# P16_USB_3_0_HUB.net
KiCad netlist of a schematic drawn in Altium Designer
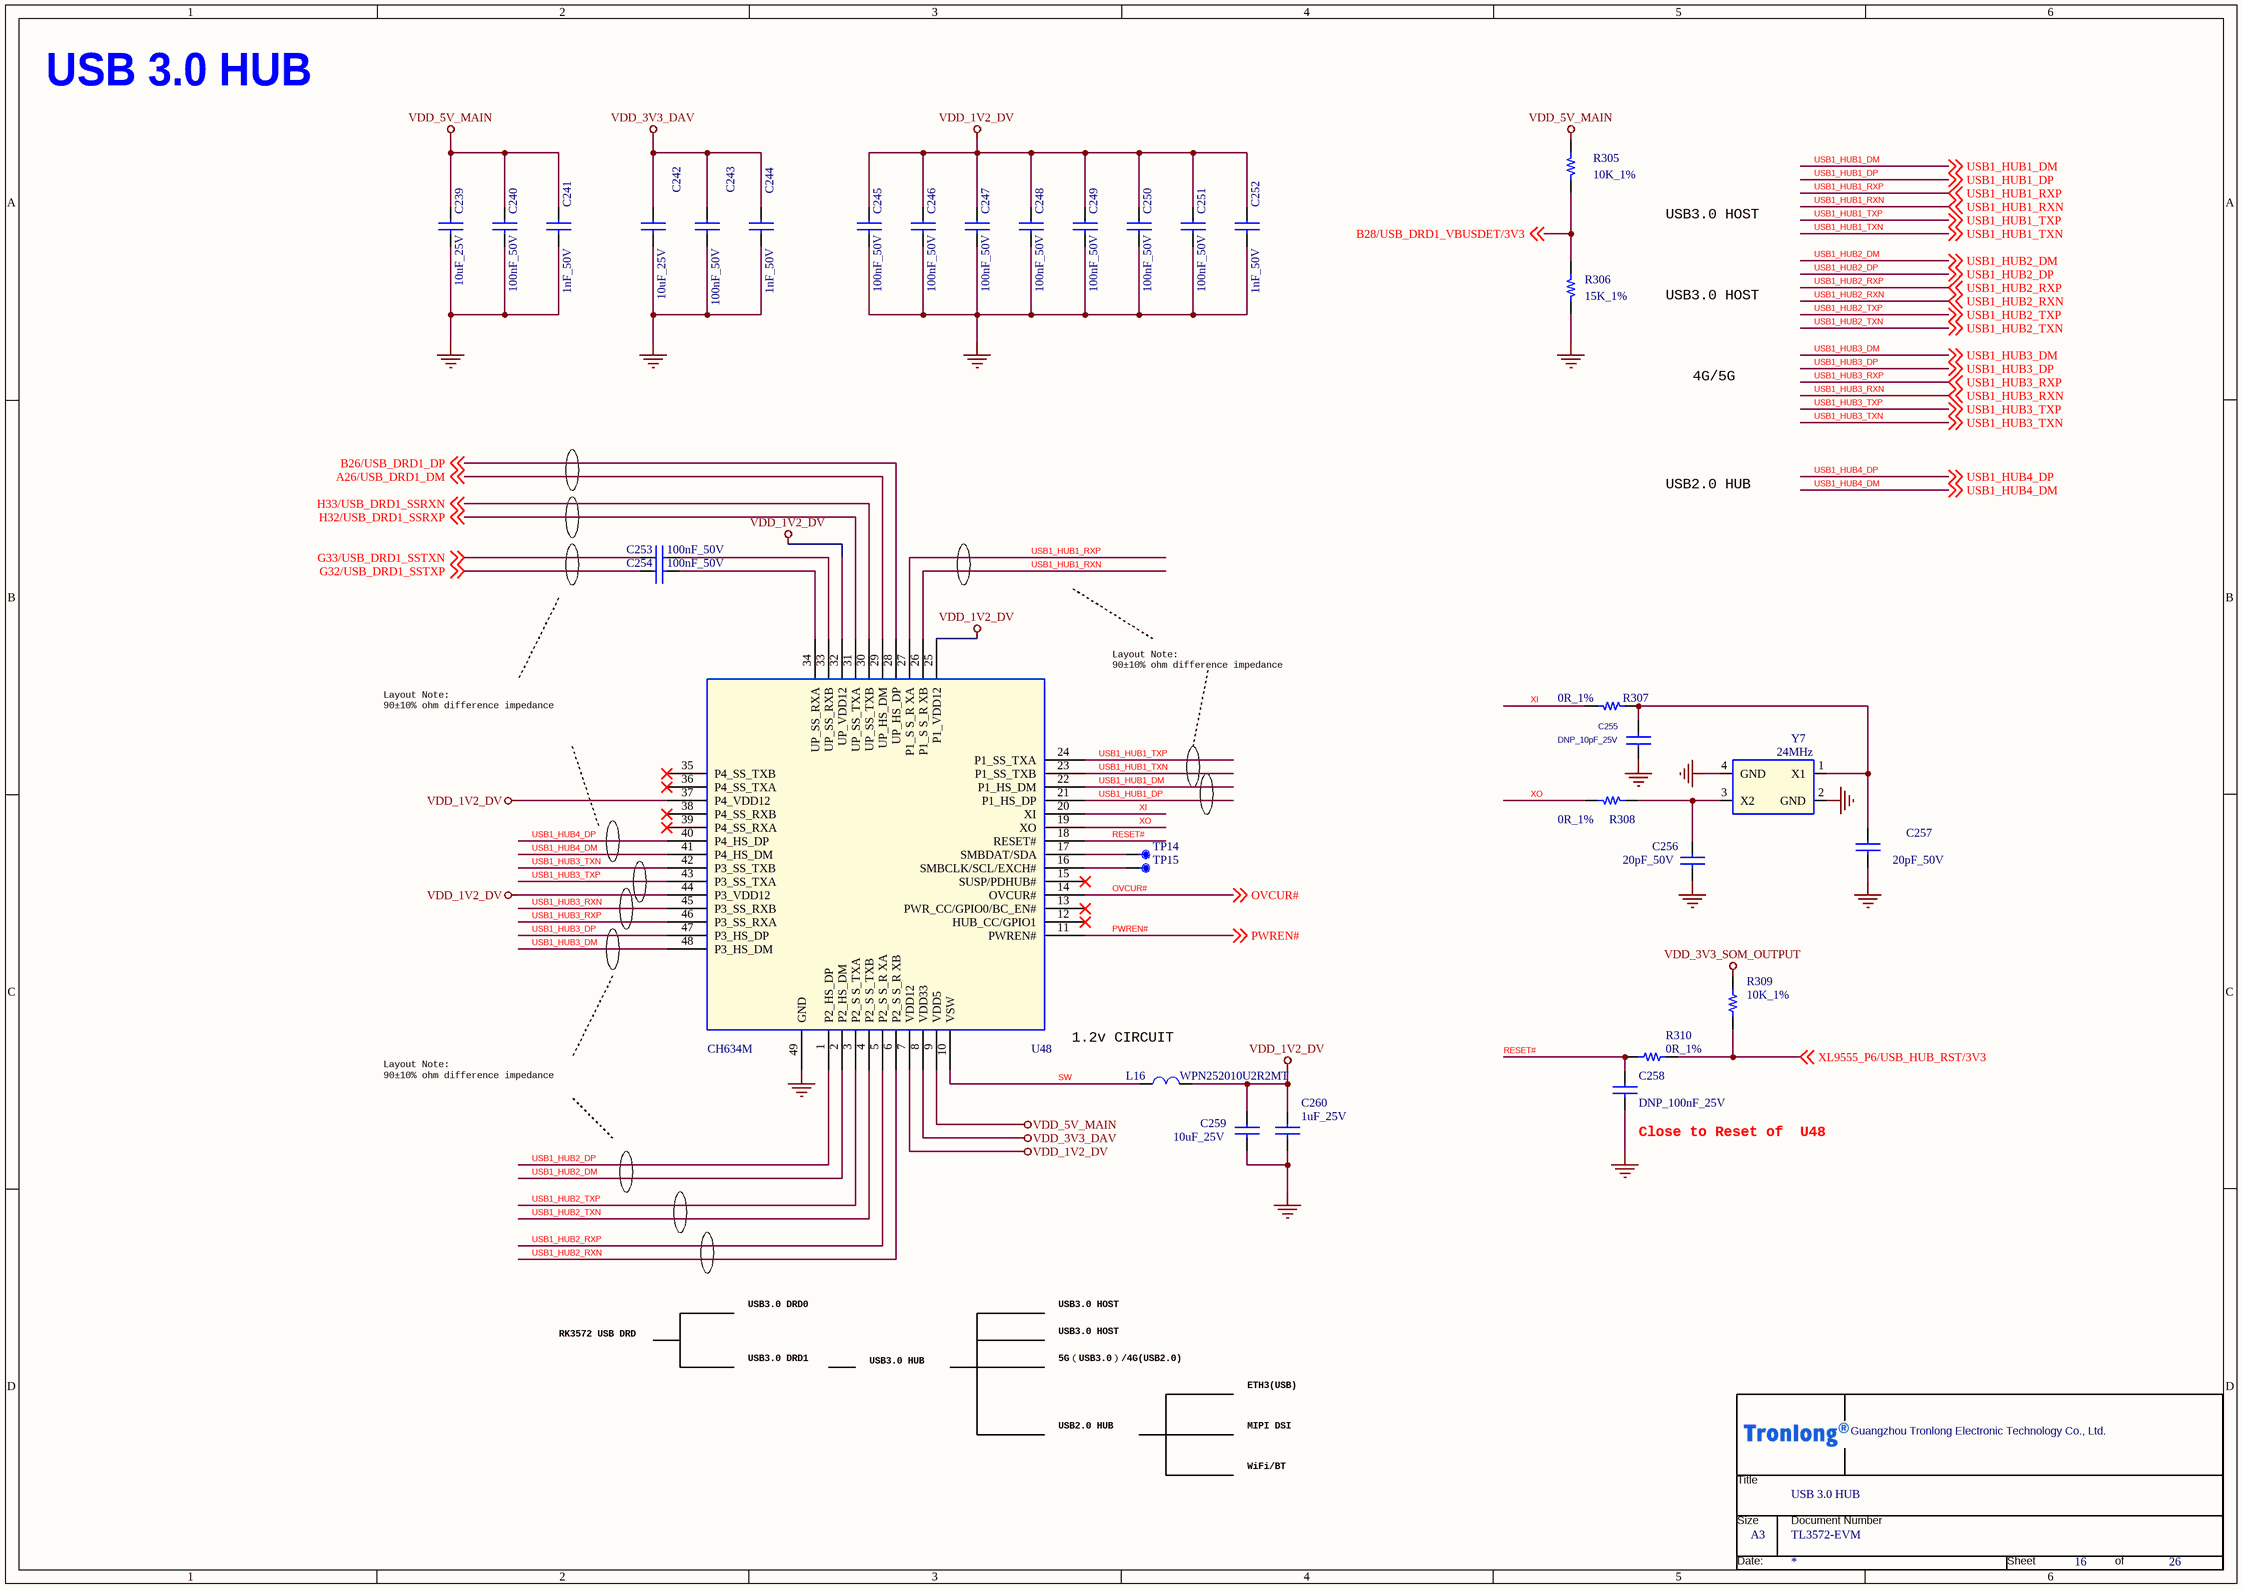
[diagram p0: P16_USB 3.0 HUB.SchDoc]

(export (version "E")
  (design (tool "Eeschema 10.0.6"))
  (components
    (comp (ref "*")
      (value "Tronlong_TITTLE_20211115")
      (fields
        (field (name "DOC") "TL3572-EVM")
        (field (name "TITLE") "USB 3.0 HUB")
        (field (name "ORGNAME") "Guangzhou Tronlong Electronic Technology Co., Ltd.")
        (field (name "PAGE SIZE") "A3")
        (field (name "PAGE NUMBER") "16")
        (field (name "PAGE COUNT") "26")
      )
      (libsource (lib "*") (part "Tronlong_TITTLE_20211115"))
    )
    (comp (ref "C239")
      (value "10uF_25V")
      (footprint "C0603")
      (description "贴片陶瓷电容,10uF,20%,25V,X5R")
      (fields
        (field (name "MANUFACTURER") "广东风华高新科技股份有限公司（FH）")
        (field (name "MANUFACTURER PARTNUMBER") "0603X106M250NT")
      )
      (libsource (lib "*") (part "CAP NP_Dup2"))
    )
    (comp (ref "C240")
      (value "100nF_50V")
      (footprint "C0402")
      (description "贴片陶瓷电容,100nF,10%,50V,X7R")
      (fields
        (field (name "MANUFACTURER PARTNUMBER") "0402B104K500NT")
        (field (name "MANUFACTURER") "广东风华高新科技股份有限公司（FH）")
      )
      (libsource (lib "*") (part "CAP NP_Dup2"))
    )
    (comp (ref "C241")
      (value "1nF_50V")
      (footprint "C0402")
      (description "贴片陶瓷电容,1nF,10%,50V,X7R")
      (fields
        (field (name "MANUFACTURER PARTNUMBER") "0402B102K500NT")
        (field (name "MANUFACTURER") "广东风华高新科技股份有限公司（FH）")
        (field (name "CREATED BY") "JJJ")
      )
      (libsource (lib "*") (part "CAP NP_1"))
    )
    (comp (ref "C242")
      (value "10uF_25V")
      (footprint "C0603")
      (description "贴片陶瓷电容,10uF,20%,25V,X5R")
      (fields
        (field (name "MANUFACTURER PARTNUMBER") "0603X106M250NT")
        (field (name "MANUFACTURER") "广东风华高新科技股份有限公司（FH）")
      )
      (libsource (lib "*") (part "CAP NP_Dup2"))
    )
    (comp (ref "C243")
      (value "100nF_50V")
      (footprint "C0402")
      (description "贴片陶瓷电容,100nF,10%,50V,X7R")
      (fields
        (field (name "MANUFACTURER PARTNUMBER") "0402B104K500NT")
        (field (name "MANUFACTURER") "广东风华高新科技股份有限公司（FH）")
      )
      (libsource (lib "*") (part "CAP NP_Dup2"))
    )
    (comp (ref "C244")
      (value "1nF_50V")
      (footprint "C0402")
      (description "贴片陶瓷电容,1nF,10%,50V,X7R")
      (fields
        (field (name "MANUFACTURER PARTNUMBER") "0402B102K500NT")
        (field (name "MANUFACTURER") "广东风华高新科技股份有限公司（FH）")
        (field (name "CREATED BY") "JJJ")
      )
      (libsource (lib "*") (part "CAP NP_1"))
    )
    (comp (ref "C245")
      (value "100nF_50V")
      (footprint "C0402")
      (description "贴片陶瓷电容,100nF,10%,50V,X7R")
      (fields
        (field (name "MANUFACTURER PARTNUMBER") "0402B104K500NT")
        (field (name "MANUFACTURER") "广东风华高新科技股份有限公司（FH）")
      )
      (libsource (lib "*") (part "CAP NP_Dup2"))
    )
    (comp (ref "C246")
      (value "100nF_50V")
      (footprint "C0402")
      (description "贴片陶瓷电容,100nF,10%,50V,X7R")
      (fields
        (field (name "MANUFACTURER PARTNUMBER") "0402B104K500NT")
        (field (name "MANUFACTURER") "广东风华高新科技股份有限公司（FH）")
      )
      (libsource (lib "*") (part "CAP NP_Dup2"))
    )
    (comp (ref "C247")
      (value "100nF_50V")
      (footprint "C0402")
      (description "贴片陶瓷电容,100nF,10%,50V,X7R")
      (fields
        (field (name "MANUFACTURER PARTNUMBER") "0402B104K500NT")
        (field (name "MANUFACTURER") "广东风华高新科技股份有限公司（FH）")
      )
      (libsource (lib "*") (part "CAP NP_Dup2"))
    )
    (comp (ref "C248")
      (value "100nF_50V")
      (footprint "C0402")
      (description "贴片陶瓷电容,100nF,10%,50V,X7R")
      (fields
        (field (name "MANUFACTURER PARTNUMBER") "0402B104K500NT")
        (field (name "MANUFACTURER") "广东风华高新科技股份有限公司（FH）")
      )
      (libsource (lib "*") (part "CAP NP_Dup2"))
    )
    (comp (ref "C249")
      (value "100nF_50V")
      (footprint "C0402")
      (description "贴片陶瓷电容,100nF,10%,50V,X7R")
      (fields
        (field (name "MANUFACTURER PARTNUMBER") "0402B104K500NT")
        (field (name "MANUFACTURER") "广东风华高新科技股份有限公司（FH）")
      )
      (libsource (lib "*") (part "CAP NP_Dup2"))
    )
    (comp (ref "C250")
      (value "100nF_50V")
      (footprint "C0402")
      (description "贴片陶瓷电容,100nF,10%,50V,X7R")
      (fields
        (field (name "MANUFACTURER PARTNUMBER") "0402B104K500NT")
        (field (name "MANUFACTURER") "广东风华高新科技股份有限公司（FH）")
      )
      (libsource (lib "*") (part "CAP NP_Dup2"))
    )
    (comp (ref "C251")
      (value "100nF_50V")
      (footprint "C0402")
      (description "贴片陶瓷电容,100nF,10%,50V,X7R")
      (fields
        (field (name "MANUFACTURER PARTNUMBER") "0402B104K500NT")
        (field (name "MANUFACTURER") "广东风华高新科技股份有限公司（FH）")
      )
      (libsource (lib "*") (part "CAP NP_Dup2"))
    )
    (comp (ref "C252")
      (value "1nF_50V")
      (footprint "C0402")
      (description "贴片陶瓷电容,1nF,10%,50V,X7R")
      (fields
        (field (name "TOLERANCE") "±20%")
        (field (name "MANUFACTURER") "广东风华高新科技股份有限公司（FH）")
        (field (name "CREATED BY") "JJJ")
      )
      (libsource (lib "*") (part "CAP NP_1"))
    )
    (comp (ref "C253")
      (value "100nF_50V")
      (footprint "C0402")
      (description "贴片陶瓷电容,100nF,10%,50V,X7R")
      (fields
        (field (name "MANUFACTURER") "广东风华高新科技股份有限公司（FH）")
        (field (name "MANUFACTURER PARTNUMBER") "0402B104K500NT")
      )
      (libsource (lib "*") (part "CAP NP_Dup2"))
    )
    (comp (ref "C254")
      (value "100nF_50V")
      (footprint "C0402")
      (description "贴片陶瓷电容,100nF,10%,50V,X7R")
      (fields
        (field (name "MANUFACTURER PARTNUMBER") "0402B104K500NT")
        (field (name "MANUFACTURER") "广东风华高新科技股份有限公司（FH）")
      )
      (libsource (lib "*") (part "CAP NP_Dup2"))
    )
    (comp (ref "C255")
      (value "DNP_10pF_25V")
      (footprint "C0402")
      (description "CL05C100JA5NNNC")
      (fields
        (field (name "MANUFACTURER PARTNUMBER") "10pF,5%,C0402,25V,（X7R,X5R,COG,NPO或X7S）")
        (field (name "MANUFACTURER") "广州创龙")
      )
      (libsource (lib "*") (part "CAP NP_Dup3"))
    )
    (comp (ref "C256")
      (value "20pF_50V")
      (footprint "C0402")
      (description "贴片陶瓷电容,20pF,5%,50V,COG")
      (fields
        (field (name "MANUFACTURER") "广东风华高新科技股份有限公司（FH）")
        (field (name "MANUFACTURER PARTNUMBER") "0402CG200J500NT")
      )
      (libsource (lib "*") (part "CAP NP_Dup2"))
    )
    (comp (ref "C257")
      (value "20pF_50V")
      (footprint "C0402")
      (description "贴片陶瓷电容,20pF,5%,50V,COG")
      (fields
        (field (name "MANUFACTURER") "广东风华高新科技股份有限公司（FH）")
        (field (name "MANUFACTURER PARTNUMBER") "0402CG200J500NT")
      )
      (libsource (lib "*") (part "CAP NP_Dup2"))
    )
    (comp (ref "C258")
      (value "DNP_100nF_25V")
      (footprint "C0402")
      (description "贴片陶瓷电容,100nF,10%,25V,X7R")
      (fields
        (field (name "MANUFACTURER") "广东风华高新科技股份有限公司（FH）")
        (field (name "TOLERANCE") "10%")
        (field (name "CREATED BY") "JJJ")
      )
      (libsource (lib "*") (part "CAP NP_Dup1"))
    )
    (comp (ref "C259")
      (value "10uF_25V")
      (footprint "C0603")
      (description "贴片陶瓷电容,10uF,20%,25V,X5R")
      (fields
        (field (name "MANUFACTURER PARTNUMBER") "0603X106M250NT")
        (field (name "MANUFACTURER") "广东风华高新科技股份有限公司（FH）")
      )
      (libsource (lib "*") (part "CAP NP_Dup2"))
    )
    (comp (ref "C260")
      (value "1uF_25V")
      (footprint "C0402")
      (description "贴片陶瓷电容,1uF,10%,25V,X5R")
      (fields
        (field (name "MANUFACTURER") "广东风华高新科技股份有限公司（FH）")
        (field (name "TOLERANCE") "±20%")
        (field (name "CREATED BY") "JJJ")
      )
      (libsource (lib "*") (part "CAP NP_1"))
    )
    (comp (ref "L16")
      (value "WPN252010U2R2MT")
      (footprint "SMD-L2520M-2P")
      (description "贴片功率电感,2.2uH,0.096Ω,Isat=2.9A,Irms=2.4A")
      (fields (field (name "MANUFACTURER") "深圳顺络电子股份有限公司（Sunlord）"))
      (libsource (lib "*") (part "FB-0805"))
    )
    (comp (ref "R305")
      (value "10K_1%")
      (footprint "R0402")
      (description "贴片电阻,10K,±1%,1/16W")
      (fields
        (field (name "MANUFACTURER") "广东风华高新科技股份有限公司（FH）")
        (field (name "MANUFACTURER PARTNUMBER") "RC-02K1002FT")
      )
      (libsource (lib "*") (part "Resistor_Dup3"))
    )
    (comp (ref "R306")
      (value "15K_1%")
      (footprint "R0402")
      (description "贴片电阻,15K,±1%,1/16W")
      (fields
        (field (name "MANUFACTURER PARTNUMBER") "RC-02K1502FT")
        (field (name "MANUFACTURER") "广东风华高新科技股份有限公司（FH）")
      )
      (libsource (lib "*") (part "Resistor_Dup3"))
    )
    (comp (ref "R307")
      (value "0R_1%")
      (footprint "R0402")
      (description "贴片电阻,0R,±1%,1/16W")
      (fields
        (field (name "MANUFACTURER PARTNUMBER") "RC-02000FT")
        (field (name "MANUFACTURER") "广东风华高新科技股份有限公司（FH）")
        (field (name "CREATED BY") "YTL")
      )
      (libsource (lib "*") (part "Resistor_Dup1"))
    )
    (comp (ref "R308")
      (value "0R_1%")
      (footprint "R0402")
      (description "贴片电阻,0R,±1%,1/16W")
      (fields
        (field (name "MANUFACTURER PARTNUMBER") "RC-02000FT")
        (field (name "MANUFACTURER") "广东风华高新科技股份有限公司（FH）")
        (field (name "CREATED BY") "YTL")
      )
      (libsource (lib "*") (part "Resistor_Dup1"))
    )
    (comp (ref "R309")
      (value "10K_1%")
      (footprint "R0402")
      (description "贴片电阻,10K,±1%,1/16W")
      (fields
        (field (name "MANUFACTURER PARTNUMBER") "RC-02K1002FT")
        (field (name "MANUFACTURER") "广东风华高新科技股份有限公司（FH）")
      )
      (libsource (lib "*") (part "Resistor_Dup3"))
    )
    (comp (ref "R310")
      (value "0R_1%")
      (footprint "R0402")
      (description "贴片电阻,0R,±1%,1/16W")
      (fields
        (field (name "MANUFACTURER PARTNUMBER") "RC-02000FT")
        (field (name "MANUFACTURER") "广东风华高新科技股份有限公司（FH）")
      )
      (libsource (lib "*") (part "Resistor_Dup3"))
    )
    (comp (ref "TP14")
      (value "SMT TP")
      (footprint "TP30")
      (description "/")
      (libsource (lib "*") (part "TP-S40"))
    )
    (comp (ref "TP15")
      (value "SMT TP")
      (footprint "TP30")
      (description "/")
      (libsource (lib "*") (part "TP-S40"))
    )
    (comp (ref "U48")
      (value "CH634M")
      (footprint "QFN48_5x5")
      (description "USB 3.2 Gen1 HUB控制器")
      (fields (field (name "MANUFACTURER") "南京沁恒微电子股份有限公司（WCH）"))
      (libsource (lib "*") (part "CH634M_0"))
    )
    (comp (ref "Y7")
      (value "24MHz")
      (footprint "SMD_3225")
      (description "四脚无源晶振,24MHz,±10ppm,12pF,100Ω,±30ppm")
      (fields
        (field (name "MANUFACTURER") "深圳市星通时频电子有限公司（SCTF）")
        (field (name "MANUFACTURER PARTNUMBER") "S3B24.000F1210F30")
        (field (name "CREATED BY") "JJJ")
      )
      (libsource (lib "*") (part "CRYSTAL_4P"))
    )
  )
  (nets
    (net (code "1") (name "/RESET#") (class "Default")
      (node (ref "C258") (pin "1") (pinfunction "1_1") (pintype "passive"))
      (node (ref "R310") (pin "2") (pinfunction "2_2") (pintype "passive"))
      (node (ref "U48") (pin "18") (pinfunction "RESET#_18") (pintype "passive"))
    )
    (net (code "2") (name "/SW") (class "Default")
      (node (ref "L16") (pin "1") (pinfunction "1_1") (pintype "passive"))
      (node (ref "U48") (pin "10") (pinfunction "VSW_10") (pintype "passive"))
    )
    (net (code "3") (name "/XI") (class "Default")
      (node (ref "R307") (pin "2") (pinfunction "2_2") (pintype "passive"))
      (node (ref "U48") (pin "20") (pinfunction "XI_20") (pintype "passive"))
    )
    (net (code "4") (name "/XO") (class "Default")
      (node (ref "R308") (pin "2") (pinfunction "2_2") (pintype "passive"))
      (node (ref "U48") (pin "19") (pinfunction "XO_19") (pintype "passive"))
    )
    (net (code "5") (name "A26{slash}USB_DRD1_DM") (class "Default")
      (node (ref "U48") (pin "29") (pinfunction "UP_HS_DM_29") (pintype "passive"))
    )
    (net (code "6") (name "B26{slash}USB_DRD1_DP") (class "Default")
      (node (ref "U48") (pin "28") (pinfunction "UP_HS_DP_28") (pintype "passive"))
    )
    (net (code "7") (name "B28{slash}USB_DRD1_VBUSDET{slash}3V3") (class "Default")
      (node (ref "R305") (pin "2") (pinfunction "2_2") (pintype "passive"))
      (node (ref "R306") (pin "1") (pinfunction "1_1") (pintype "passive"))
    )
    (net (code "8") (name "G32{slash}USB_DRD1_SSTXP") (class "Default")
      (node (ref "C254") (pin "1") (pinfunction "1_1") (pintype "passive"))
    )
    (net (code "9") (name "G33{slash}USB_DRD1_SSTXN") (class "Default")
      (node (ref "C253") (pin "1") (pinfunction "1_1") (pintype "passive"))
    )
    (net (code "10") (name "GND") (class "Default")
      (node (ref "C239") (pin "2") (pinfunction "2_2") (pintype "passive"))
      (node (ref "C240") (pin "2") (pinfunction "2_2") (pintype "passive"))
      (node (ref "C241") (pin "2") (pinfunction "2_2") (pintype "passive"))
      (node (ref "C242") (pin "2") (pinfunction "2_2") (pintype "passive"))
      (node (ref "C243") (pin "2") (pinfunction "2_2") (pintype "passive"))
      (node (ref "C244") (pin "2") (pinfunction "2_2") (pintype "passive"))
      (node (ref "C245") (pin "2") (pinfunction "2_2") (pintype "passive"))
      (node (ref "C246") (pin "2") (pinfunction "2_2") (pintype "passive"))
      (node (ref "C247") (pin "2") (pinfunction "2_2") (pintype "passive"))
      (node (ref "C248") (pin "2") (pinfunction "2_2") (pintype "passive"))
      (node (ref "C249") (pin "2") (pinfunction "2_2") (pintype "passive"))
      (node (ref "C250") (pin "2") (pinfunction "2_2") (pintype "passive"))
      (node (ref "C251") (pin "2") (pinfunction "2_2") (pintype "passive"))
      (node (ref "C252") (pin "2") (pinfunction "2_2") (pintype "passive"))
      (node (ref "C255") (pin "1") (pinfunction "1_1") (pintype "passive"))
      (node (ref "C256") (pin "2") (pinfunction "2_2") (pintype "passive"))
      (node (ref "C257") (pin "2") (pinfunction "2_2") (pintype "passive"))
      (node (ref "C258") (pin "2") (pinfunction "2_2") (pintype "passive"))
      (node (ref "C259") (pin "2") (pinfunction "2_2") (pintype "passive"))
      (node (ref "C260") (pin "2") (pinfunction "2_2") (pintype "passive"))
      (node (ref "R306") (pin "2") (pinfunction "2_2") (pintype "passive"))
      (node (ref "U48") (pin "49") (pinfunction "GND_49") (pintype "passive"))
      (node (ref "Y7") (pin "2") (pinfunction "GND_2") (pintype "power_in"))
      (node (ref "Y7") (pin "4") (pinfunction "GND_4") (pintype "power_in"))
    )
    (net (code "11") (name "H32{slash}USB_DRD1_SSRXP") (class "Default")
      (node (ref "U48") (pin "31") (pinfunction "UP_SS_TXA_31") (pintype "passive"))
    )
    (net (code "12") (name "H33{slash}USB_DRD1_SSRXN") (class "Default")
      (node (ref "U48") (pin "30") (pinfunction "UP_SS_TXB_30") (pintype "passive"))
    )
    (net (code "13") (name "Net-(U48-SMBCLK{slash}SCL{slash}EXCH#)") (class "Default")
      (node (ref "TP15") (pin "1") (pinfunction "1_1") (pintype "passive"))
      (node (ref "U48") (pin "16") (pinfunction "SMBCLK/SCL/EXCH#_16") (pintype "passive"))
    )
    (net (code "14") (name "Net-(U48-SMBDAT{slash}SDA)") (class "Default")
      (node (ref "TP14") (pin "1") (pinfunction "1_1") (pintype "passive"))
      (node (ref "U48") (pin "17") (pinfunction "SMBDAT/SDA_17") (pintype "passive"))
    )
    (net (code "15") (name "Net-(U48-UP_SS_RXA)") (class "Default")
      (node (ref "C254") (pin "2") (pinfunction "2_2") (pintype "passive"))
      (node (ref "U48") (pin "34") (pinfunction "UP_SS_RXA_34") (pintype "passive"))
    )
    (net (code "16") (name "Net-(U48-UP_SS_RXB)") (class "Default")
      (node (ref "C253") (pin "2") (pinfunction "2_2") (pintype "passive"))
      (node (ref "U48") (pin "33") (pinfunction "UP_SS_RXB_33") (pintype "passive"))
    )
    (net (code "17") (name "Net-(Y7-X1)") (class "Default")
      (node (ref "C255") (pin "2") (pinfunction "2_2") (pintype "passive"))
      (node (ref "C257") (pin "1") (pinfunction "1_1") (pintype "passive"))
      (node (ref "R307") (pin "1") (pinfunction "1_1") (pintype "passive"))
      (node (ref "Y7") (pin "1") (pinfunction "X1_1") (pintype "passive"))
    )
    (net (code "18") (name "Net-(Y7-X2)") (class "Default")
      (node (ref "C256") (pin "1") (pinfunction "1_1") (pintype "passive"))
      (node (ref "R308") (pin "1") (pinfunction "1_1") (pintype "passive"))
      (node (ref "Y7") (pin "3") (pinfunction "X2_3") (pintype "passive"))
    )
    (net (code "19") (name "OVCUR#") (class "Default")
      (node (ref "U48") (pin "14") (pinfunction "OVCUR#_14") (pintype "passive"))
    )
    (net (code "20") (name "PWREN#") (class "Default")
      (node (ref "U48") (pin "11") (pinfunction "PWREN#_11") (pintype "passive"))
    )
    (net (code "21") (name "USB1_HUB1_DM") (class "Default")
      (node (ref "U48") (pin "22") (pinfunction "P1_HS_DM_22") (pintype "passive"))
    )
    (net (code "22") (name "USB1_HUB1_DP") (class "Default")
      (node (ref "U48") (pin "21") (pinfunction "P1_HS_DP_21") (pintype "passive"))
    )
    (net (code "23") (name "USB1_HUB1_RXN") (class "Default")
      (node (ref "U48") (pin "26") (pinfunction "P1_S_S_R_XB_26") (pintype "passive"))
    )
    (net (code "24") (name "USB1_HUB1_RXP") (class "Default")
      (node (ref "U48") (pin "27") (pinfunction "P1_S_S_R_XA_27") (pintype "passive"))
    )
    (net (code "25") (name "USB1_HUB1_TXN") (class "Default")
      (node (ref "U48") (pin "23") (pinfunction "P1_SS_TXB_23") (pintype "passive"))
    )
    (net (code "26") (name "USB1_HUB1_TXP") (class "Default")
      (node (ref "U48") (pin "24") (pinfunction "P1_SS_TXA_24") (pintype "passive"))
    )
    (net (code "27") (name "USB1_HUB2_DM") (class "Default")
      (node (ref "U48") (pin "2") (pinfunction "P2_HS_DM_2") (pintype "passive"))
    )
    (net (code "28") (name "USB1_HUB2_DP") (class "Default")
      (node (ref "U48") (pin "1") (pinfunction "P2_HS_DP_1") (pintype "passive"))
    )
    (net (code "29") (name "USB1_HUB2_RXN") (class "Default")
      (node (ref "U48") (pin "6") (pinfunction "P2_S_S_R_XB_6") (pintype "passive"))
    )
    (net (code "30") (name "USB1_HUB2_RXP") (class "Default")
      (node (ref "U48") (pin "5") (pinfunction "P2_S_S_R_XA_5") (pintype "passive"))
    )
    (net (code "31") (name "USB1_HUB2_TXN") (class "Default")
      (node (ref "U48") (pin "4") (pinfunction "P2_S_S_TXB_4") (pintype "passive"))
    )
    (net (code "32") (name "USB1_HUB2_TXP") (class "Default")
      (node (ref "U48") (pin "3") (pinfunction "P2_S_S_TXA_3") (pintype "passive"))
    )
    (net (code "33") (name "USB1_HUB3_DM") (class "Default")
      (node (ref "U48") (pin "48") (pinfunction "P3_HS_DM_48") (pintype "passive"))
    )
    (net (code "34") (name "USB1_HUB3_DP") (class "Default")
      (node (ref "U48") (pin "47") (pinfunction "P3_HS_DP_47") (pintype "passive"))
    )
    (net (code "35") (name "USB1_HUB3_RXN") (class "Default")
      (node (ref "U48") (pin "45") (pinfunction "P3_SS_RXB_45") (pintype "passive"))
    )
    (net (code "36") (name "USB1_HUB3_RXP") (class "Default")
      (node (ref "U48") (pin "46") (pinfunction "P3_SS_RXA_46") (pintype "passive"))
    )
    (net (code "37") (name "USB1_HUB3_TXN") (class "Default")
      (node (ref "U48") (pin "42") (pinfunction "P3_SS_TXB_42") (pintype "passive"))
    )
    (net (code "38") (name "USB1_HUB3_TXP") (class "Default")
      (node (ref "U48") (pin "43") (pinfunction "P3_SS_TXA_43") (pintype "passive"))
    )
    (net (code "39") (name "USB1_HUB4_DM") (class "Default")
      (node (ref "U48") (pin "41") (pinfunction "P4_HS_DM_41") (pintype "passive"))
    )
    (net (code "40") (name "USB1_HUB4_DP") (class "Default")
      (node (ref "U48") (pin "40") (pinfunction "P4_HS_DP_40") (pintype "passive"))
    )
    (net (code "41") (name "VDD_1V2_DV") (class "Default")
      (node (ref "C245") (pin "1") (pinfunction "1_1") (pintype "passive"))
      (node (ref "C246") (pin "1") (pinfunction "1_1") (pintype "passive"))
      (node (ref "C247") (pin "1") (pinfunction "1_1") (pintype "passive"))
      (node (ref "C248") (pin "1") (pinfunction "1_1") (pintype "passive"))
      (node (ref "C249") (pin "1") (pinfunction "1_1") (pintype "passive"))
      (node (ref "C250") (pin "1") (pinfunction "1_1") (pintype "passive"))
      (node (ref "C251") (pin "1") (pinfunction "1_1") (pintype "passive"))
      (node (ref "C252") (pin "1") (pinfunction "1_1") (pintype "passive"))
      (node (ref "C259") (pin "1") (pinfunction "1_1") (pintype "passive"))
      (node (ref "C260") (pin "1") (pinfunction "1_1") (pintype "passive"))
      (node (ref "L16") (pin "2") (pinfunction "2_2") (pintype "passive"))
      (node (ref "U48") (pin "25") (pinfunction "P1_VDD12_25") (pintype "passive"))
      (node (ref "U48") (pin "32") (pinfunction "UP_VDD12_32") (pintype "passive"))
      (node (ref "U48") (pin "37") (pinfunction "P4_VDD12_37") (pintype "passive"))
      (node (ref "U48") (pin "44") (pinfunction "P3_VDD12_44") (pintype "passive"))
      (node (ref "U48") (pin "7") (pinfunction "VDD12_7") (pintype "passive"))
    )
    (net (code "42") (name "VDD_3V3_DAV") (class "Default")
      (node (ref "C242") (pin "1") (pinfunction "1_1") (pintype "passive"))
      (node (ref "C243") (pin "1") (pinfunction "1_1") (pintype "passive"))
      (node (ref "C244") (pin "1") (pinfunction "1_1") (pintype "passive"))
      (node (ref "U48") (pin "8") (pinfunction "VDD33_8") (pintype "passive"))
    )
    (net (code "43") (name "VDD_3V3_SOM_OUTPUT") (class "Default")
      (node (ref "R309") (pin "1") (pinfunction "1_1") (pintype "passive"))
    )
    (net (code "44") (name "VDD_5V_MAIN") (class "Default")
      (node (ref "C239") (pin "1") (pinfunction "1_1") (pintype "passive"))
      (node (ref "C240") (pin "1") (pinfunction "1_1") (pintype "passive"))
      (node (ref "C241") (pin "1") (pinfunction "1_1") (pintype "passive"))
      (node (ref "R305") (pin "1") (pinfunction "1_1") (pintype "passive"))
      (node (ref "U48") (pin "9") (pinfunction "VDD5_9") (pintype "passive"))
    )
    (net (code "45") (name "XL9555_P6{slash}USB_HUB_RST{slash}3V3") (class "Default")
      (node (ref "R309") (pin "2") (pinfunction "2_2") (pintype "passive"))
      (node (ref "R310") (pin "1") (pinfunction "1_1") (pintype "passive"))
    )
    (net (code "46") (name "unconnected-(U48-HUB_CC{slash}GPIO1-Pad12)") (class "Default")
      (node (ref "U48") (pin "12") (pinfunction "HUB_CC/GPIO1_12") (pintype "passive+no_connect"))
    )
    (net (code "47") (name "unconnected-(U48-P4_SS_RXA-Pad39)") (class "Default")
      (node (ref "U48") (pin "39") (pinfunction "P4_SS_RXA_39") (pintype "passive+no_connect"))
    )
    (net (code "48") (name "unconnected-(U48-P4_SS_RXB-Pad38)") (class "Default")
      (node (ref "U48") (pin "38") (pinfunction "P4_SS_RXB_38") (pintype "passive+no_connect"))
    )
    (net (code "49") (name "unconnected-(U48-P4_SS_TXA-Pad36)") (class "Default")
      (node (ref "U48") (pin "36") (pinfunction "P4_SS_TXA_36") (pintype "passive+no_connect"))
    )
    (net (code "50") (name "unconnected-(U48-P4_SS_TXB-Pad35)") (class "Default")
      (node (ref "U48") (pin "35") (pinfunction "P4_SS_TXB_35") (pintype "passive+no_connect"))
    )
    (net (code "51") (name "unconnected-(U48-PWR_CC{slash}GPIO0{slash}BC_EN#-Pad13)") (class "Default")
      (node (ref "U48") (pin "13") (pinfunction "PWR_CC/GPIO0/BC_EN#_13") (pintype "passive+no_connect"))
    )
    (net (code "52") (name "unconnected-(U48-SUSP{slash}PDHUB#-Pad15)") (class "Default")
      (node (ref "U48") (pin "15") (pinfunction "SUSP/PDHUB#_15") (pintype "passive+no_connect"))
    )
  )
)
